# tinyRF.net
KiCad netlist of a schematic drawn in EAGLE
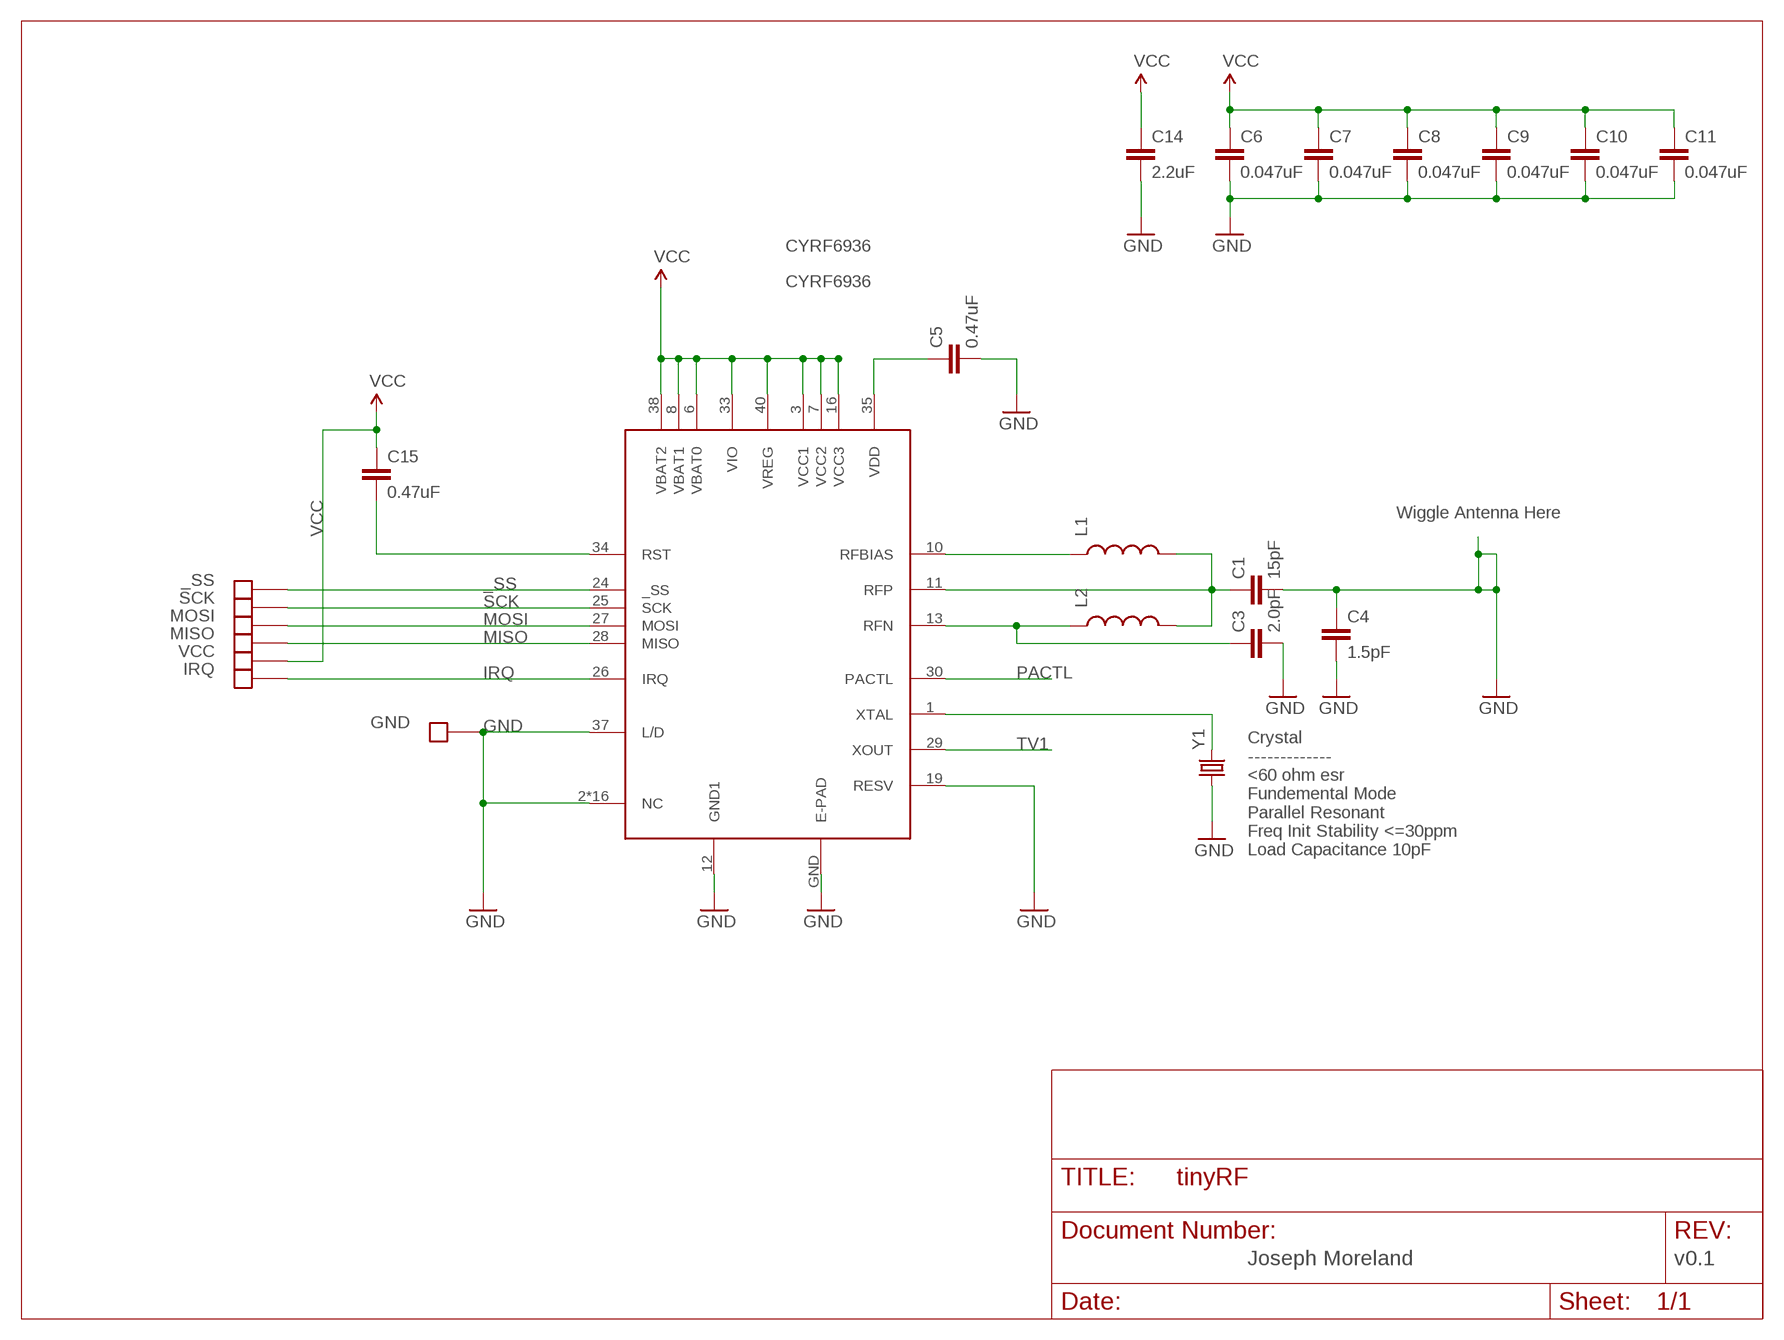
[diagram p0: schematic, sheet 1]

(export (version "E")
  (design (tool "Eeschema 10.0.6"))
  (components
    (comp (ref "C1")
      (value "15pF")
      (footprint "eagle-import:0402-CAP")
      (fields (field (name "PARTNO") "C0402C150J5GACTU"))
      (libsource (lib "eagle-import") (part "CAP0402-CAP"))
    )
    (comp (ref "C3")
      (value "2.0pF")
      (footprint "eagle-import:0402-CAP")
      (fields (field (name "PARTNO") "C0402C209C5GACTU"))
      (libsource (lib "eagle-import") (part "CAP0402-CAP"))
    )
    (comp (ref "C4")
      (value "1.5pF")
      (footprint "eagle-import:0402-CAP")
      (fields (field (name "PARTNO") "C0402C159B5GACTU"))
      (libsource (lib "eagle-import") (part "CAP0402-CAP"))
    )
    (comp (ref "C5")
      (value "0.47uF")
      (footprint "eagle-import:0402-CAP")
      (fields (field (name "PARTNO") "GRM155R60J474KE19D"))
      (libsource (lib "eagle-import") (part "CAP0402-CAP"))
    )
    (comp (ref "C6")
      (value "0.047uF")
      (footprint "eagle-import:0402-CAP")
      (fields (field (name "PARTNO") "0402YD473KAT2A"))
      (libsource (lib "eagle-import") (part "CAP0402-CAP"))
    )
    (comp (ref "C7")
      (value "0.047uF")
      (footprint "eagle-import:0402-CAP")
      (fields (field (name "PARTNO") "0402YD473KAT2A"))
      (libsource (lib "eagle-import") (part "CAP0402-CAP"))
    )
    (comp (ref "C8")
      (value "0.047uF")
      (footprint "eagle-import:0402-CAP")
      (fields (field (name "PARTNO") "0402YD473KAT2A"))
      (libsource (lib "eagle-import") (part "CAP0402-CAP"))
    )
    (comp (ref "C9")
      (value "0.047uF")
      (footprint "eagle-import:0402-CAP")
      (fields (field (name "PARTNO") "0402YD473KAT2A"))
      (libsource (lib "eagle-import") (part "CAP0402-CAP"))
    )
    (comp (ref "C10")
      (value "0.047uF")
      (footprint "eagle-import:0402-CAP")
      (fields (field (name "PARTNO") "0402YD473KAT2A"))
      (libsource (lib "eagle-import") (part "CAP0402-CAP"))
    )
    (comp (ref "C11")
      (value "0.047uF")
      (footprint "eagle-import:0402-CAP")
      (fields (field (name "PARTNO") "0402YD473KAT2A"))
      (libsource (lib "eagle-import") (part "CAP0402-CAP"))
    )
    (comp (ref "C14")
      (value "2.2uF")
      (footprint "eagle-import:0805")
      (fields (field (name "PARTNO") "GRM21BR71A225KA01L"))
      (libsource (lib "eagle-import") (part "CAP0805"))
    )
    (comp (ref "C15")
      (value "0.47uF")
      (footprint "eagle-import:0402-CAP")
      (fields (field (name "PARTNO") "GRM155R60J474KE19D"))
      (libsource (lib "eagle-import") (part "CAP0402-CAP"))
    )
    (comp (ref "CYRF6936")
      (value "CYRF6936")
      (footprint "eagle-import:QFN40")
      (fields (field (name "PARTNO") "CYRF6936B-40LTXC"))
      (libsource (lib "eagle-import") (part "CYRF6936"))
    )
    (comp (ref "GND")
      (value "SOLDER_PAD.05X.05")
      (footprint "eagle-import:SOLDER_PAD_.05X.05")
      (libsource (lib "eagle-import") (part "SOLDER_PAD.05X.05"))
    )
    (comp (ref "IRQ")
      (value "SOLDER_PAD.05X.05")
      (footprint "eagle-import:SOLDER_PAD_.05X.05")
      (libsource (lib "eagle-import") (part "SOLDER_PAD.05X.05"))
    )
    (comp (ref "L1")
      (value "INDUCTOR0603")
      (footprint "eagle-import:0603")
      (fields (field (name "PARTNO") "ELJ-RE22NGFA"))
      (libsource (lib "eagle-import") (part "INDUCTOR0603"))
    )
    (comp (ref "L2")
      (value "INDUCTOR0402")
      (footprint "eagle-import:C0402")
      (fields (field (name "PARTNO") "ELJ-RF1N8DFB"))
      (libsource (lib "eagle-import") (part "INDUCTOR0402"))
    )
    (comp (ref "MISO")
      (value "SOLDER_PAD.05X.05")
      (footprint "eagle-import:SOLDER_PAD_.05X.05")
      (libsource (lib "eagle-import") (part "SOLDER_PAD.05X.05"))
    )
    (comp (ref "MOSI")
      (value "SOLDER_PAD.05X.05")
      (footprint "eagle-import:SOLDER_PAD_.05X.05")
      (libsource (lib "eagle-import") (part "SOLDER_PAD.05X.05"))
    )
    (comp (ref "SCK")
      (value "SOLDER_PAD.05X.05")
      (footprint "eagle-import:SOLDER_PAD_.05X.05")
      (libsource (lib "eagle-import") (part "SOLDER_PAD.05X.05"))
    )
    (comp (ref "VCC")
      (value "SOLDER_PAD.05X.05")
      (footprint "eagle-import:SOLDER_PAD_.05X.05")
      (libsource (lib "eagle-import") (part "SOLDER_PAD.05X.05"))
    )
    (comp (ref "Y1")
      (value "CRYSTAL5X3")
      (footprint "eagle-import:CRYSTAL-SMD-5X3")
      (fields (field (name "PARTNO") "7B-12.000MEEQ-T"))
      (libsource (lib "eagle-import") (part "CRYSTAL5X3"))
    )
    (comp (ref "_SS")
      (value "SOLDER_PAD.05X.05")
      (footprint "eagle-import:SOLDER_PAD_.05X.05")
      (libsource (lib "eagle-import") (part "SOLDER_PAD.05X.05"))
    )
  )
  (nets
    (net (code "1") (name "/IRQ") (class "Default")
      (node (ref "CYRF6936") (pin "26") (pinfunction "IRQ_26") (pintype "bidirectional"))
      (node (ref "IRQ") (pin "P$1") (pinfunction "NET_P$1") (pintype "bidirectional"))
    )
    (net (code "2") (name "/MISO") (class "Default")
      (node (ref "CYRF6936") (pin "28") (pinfunction "MISO_28") (pintype "bidirectional"))
      (node (ref "MISO") (pin "P$1") (pinfunction "NET_P$1") (pintype "bidirectional"))
    )
    (net (code "3") (name "/MOSI") (class "Default")
      (node (ref "CYRF6936") (pin "27") (pinfunction "MOSI_27") (pintype "bidirectional"))
      (node (ref "MOSI") (pin "P$1") (pinfunction "NET_P$1") (pintype "bidirectional"))
    )
    (net (code "4") (name "/PACTL") (class "Default")
      (node (ref "CYRF6936") (pin "30") (pinfunction "PACTL_30") (pintype "bidirectional"))
    )
    (net (code "5") (name "/SCK") (class "Default")
      (node (ref "CYRF6936") (pin "25") (pinfunction "SCK_25") (pintype "bidirectional"))
      (node (ref "SCK") (pin "P$1") (pinfunction "NET_P$1") (pintype "bidirectional"))
    )
    (net (code "6") (name "/TV1") (class "Default")
      (node (ref "CYRF6936") (pin "29") (pinfunction "XOUT_29") (pintype "bidirectional"))
    )
    (net (code "7") (name "/_SS") (class "Default")
      (node (ref "CYRF6936") (pin "24") (pinfunction "_SS_24") (pintype "bidirectional"))
      (node (ref "_SS") (pin "P$1") (pinfunction "NET_P$1") (pintype "bidirectional"))
    )
    (net (code "8") (name "GND") (class "Default")
      (node (ref "C1") (pin "2") (pinfunction "2_2") (pintype "passive"))
      (node (ref "C10") (pin "2") (pinfunction "2_2") (pintype "passive"))
      (node (ref "C11") (pin "2") (pinfunction "2_2") (pintype "passive"))
      (node (ref "C14") (pin "2") (pinfunction "2_2") (pintype "passive"))
      (node (ref "C3") (pin "2") (pinfunction "2_2") (pintype "passive"))
      (node (ref "C4") (pin "1") (pinfunction "1_1") (pintype "passive"))
      (node (ref "C4") (pin "2") (pinfunction "2_2") (pintype "passive"))
      (node (ref "C5") (pin "2") (pinfunction "2_2") (pintype "passive"))
      (node (ref "C6") (pin "2") (pinfunction "2_2") (pintype "passive"))
      (node (ref "C7") (pin "2") (pinfunction "2_2") (pintype "passive"))
      (node (ref "C8") (pin "2") (pinfunction "2_2") (pintype "passive"))
      (node (ref "C9") (pin "2") (pinfunction "2_2") (pintype "passive"))
      (node (ref "CYRF6936") (pin "12") (pinfunction "GND1_12") (pintype "bidirectional"))
      (node (ref "CYRF6936") (pin "14") (pinfunction "NC_14") (pintype "bidirectional"))
      (node (ref "CYRF6936") (pin "15") (pinfunction "NC_15") (pintype "bidirectional"))
      (node (ref "CYRF6936") (pin "17") (pinfunction "NC_17") (pintype "bidirectional"))
      (node (ref "CYRF6936") (pin "18") (pinfunction "NC_18") (pintype "bidirectional"))
      (node (ref "CYRF6936") (pin "19") (pinfunction "RESV_19") (pintype "bidirectional"))
      (node (ref "CYRF6936") (pin "2") (pinfunction "NC_2") (pintype "bidirectional"))
      (node (ref "CYRF6936") (pin "20") (pinfunction "NC_20") (pintype "bidirectional"))
      (node (ref "CYRF6936") (pin "21") (pinfunction "NC_21") (pintype "bidirectional"))
      (node (ref "CYRF6936") (pin "22") (pinfunction "NC_22") (pintype "bidirectional"))
      (node (ref "CYRF6936") (pin "23") (pinfunction "NC_23") (pintype "bidirectional"))
      (node (ref "CYRF6936") (pin "31") (pinfunction "NC_31") (pintype "bidirectional"))
      (node (ref "CYRF6936") (pin "32") (pinfunction "NC_32") (pintype "bidirectional"))
      (node (ref "CYRF6936") (pin "36") (pinfunction "NC_36") (pintype "bidirectional"))
      (node (ref "CYRF6936") (pin "37") (pinfunction "L/D_37") (pintype "bidirectional"))
      (node (ref "CYRF6936") (pin "39") (pinfunction "NC_39") (pintype "bidirectional"))
      (node (ref "CYRF6936") (pin "4") (pinfunction "NC_4") (pintype "bidirectional"))
      (node (ref "CYRF6936") (pin "5") (pinfunction "NC_5") (pintype "bidirectional"))
      (node (ref "CYRF6936") (pin "9") (pinfunction "NC_9") (pintype "bidirectional"))
      (node (ref "CYRF6936") (pin "GND") (pinfunction "E-PAD_GND") (pintype "bidirectional"))
      (node (ref "GND") (pin "P$1") (pinfunction "NET_P$1") (pintype "bidirectional"))
      (node (ref "Y1") (pin "1") (pinfunction "1_1") (pintype "passive"))
    )
    (net (code "9") (name "Net-(CYRF6936-RFBIAS)") (class "Default")
      (node (ref "CYRF6936") (pin "10") (pinfunction "RFBIAS_10") (pintype "bidirectional"))
      (node (ref "L1") (pin "1") (pinfunction "1_1") (pintype "passive"))
    )
    (net (code "10") (name "Net-(CYRF6936-RFN)") (class "Default")
      (node (ref "C3") (pin "1") (pinfunction "1_1") (pintype "passive"))
      (node (ref "CYRF6936") (pin "13") (pinfunction "RFN_13") (pintype "bidirectional"))
      (node (ref "L2") (pin "1") (pinfunction "1_1") (pintype "passive"))
    )
    (net (code "11") (name "Net-(CYRF6936-RFP)") (class "Default")
      (node (ref "C1") (pin "1") (pinfunction "1_1") (pintype "passive"))
      (node (ref "CYRF6936") (pin "11") (pinfunction "RFP_11") (pintype "bidirectional"))
      (node (ref "L1") (pin "2") (pinfunction "2_2") (pintype "passive"))
      (node (ref "L2") (pin "2") (pinfunction "2_2") (pintype "passive"))
    )
    (net (code "12") (name "Net-(CYRF6936-RST)") (class "Default")
      (node (ref "C15") (pin "2") (pinfunction "2_2") (pintype "passive"))
      (node (ref "CYRF6936") (pin "34") (pinfunction "RST_34") (pintype "bidirectional"))
    )
    (net (code "13") (name "Net-(CYRF6936-VDD)") (class "Default")
      (node (ref "C5") (pin "1") (pinfunction "1_1") (pintype "passive"))
      (node (ref "CYRF6936") (pin "35") (pinfunction "VDD_35") (pintype "bidirectional"))
    )
    (net (code "14") (name "Net-(CYRF6936-XTAL)") (class "Default")
      (node (ref "CYRF6936") (pin "1") (pinfunction "XTAL_1") (pintype "bidirectional"))
      (node (ref "Y1") (pin "3") (pinfunction "2_3") (pintype "passive"))
    )
    (net (code "15") (name "VCC") (class "Default")
      (node (ref "C10") (pin "1") (pinfunction "1_1") (pintype "passive"))
      (node (ref "C11") (pin "1") (pinfunction "1_1") (pintype "passive"))
      (node (ref "C14") (pin "1") (pinfunction "1_1") (pintype "passive"))
      (node (ref "C15") (pin "1") (pinfunction "1_1") (pintype "passive"))
      (node (ref "C6") (pin "1") (pinfunction "1_1") (pintype "passive"))
      (node (ref "C7") (pin "1") (pinfunction "1_1") (pintype "passive"))
      (node (ref "C8") (pin "1") (pinfunction "1_1") (pintype "passive"))
      (node (ref "C9") (pin "1") (pinfunction "1_1") (pintype "passive"))
      (node (ref "CYRF6936") (pin "16") (pinfunction "VCC3_16") (pintype "bidirectional"))
      (node (ref "CYRF6936") (pin "3") (pinfunction "VCC1_3") (pintype "bidirectional"))
      (node (ref "CYRF6936") (pin "33") (pinfunction "VIO_33") (pintype "bidirectional"))
      (node (ref "CYRF6936") (pin "38") (pinfunction "VBAT2_38") (pintype "bidirectional"))
      (node (ref "CYRF6936") (pin "40") (pinfunction "VREG_40") (pintype "bidirectional"))
      (node (ref "CYRF6936") (pin "6") (pinfunction "VBAT0_6") (pintype "bidirectional"))
      (node (ref "CYRF6936") (pin "7") (pinfunction "VCC2_7") (pintype "bidirectional"))
      (node (ref "CYRF6936") (pin "8") (pinfunction "VBAT1_8") (pintype "bidirectional"))
      (node (ref "VCC") (pin "P$1") (pinfunction "NET_P$1") (pintype "bidirectional"))
    )
  )
)
